# ANALOG.net
KiCad netlist of a schematic drawn in Altium Designer
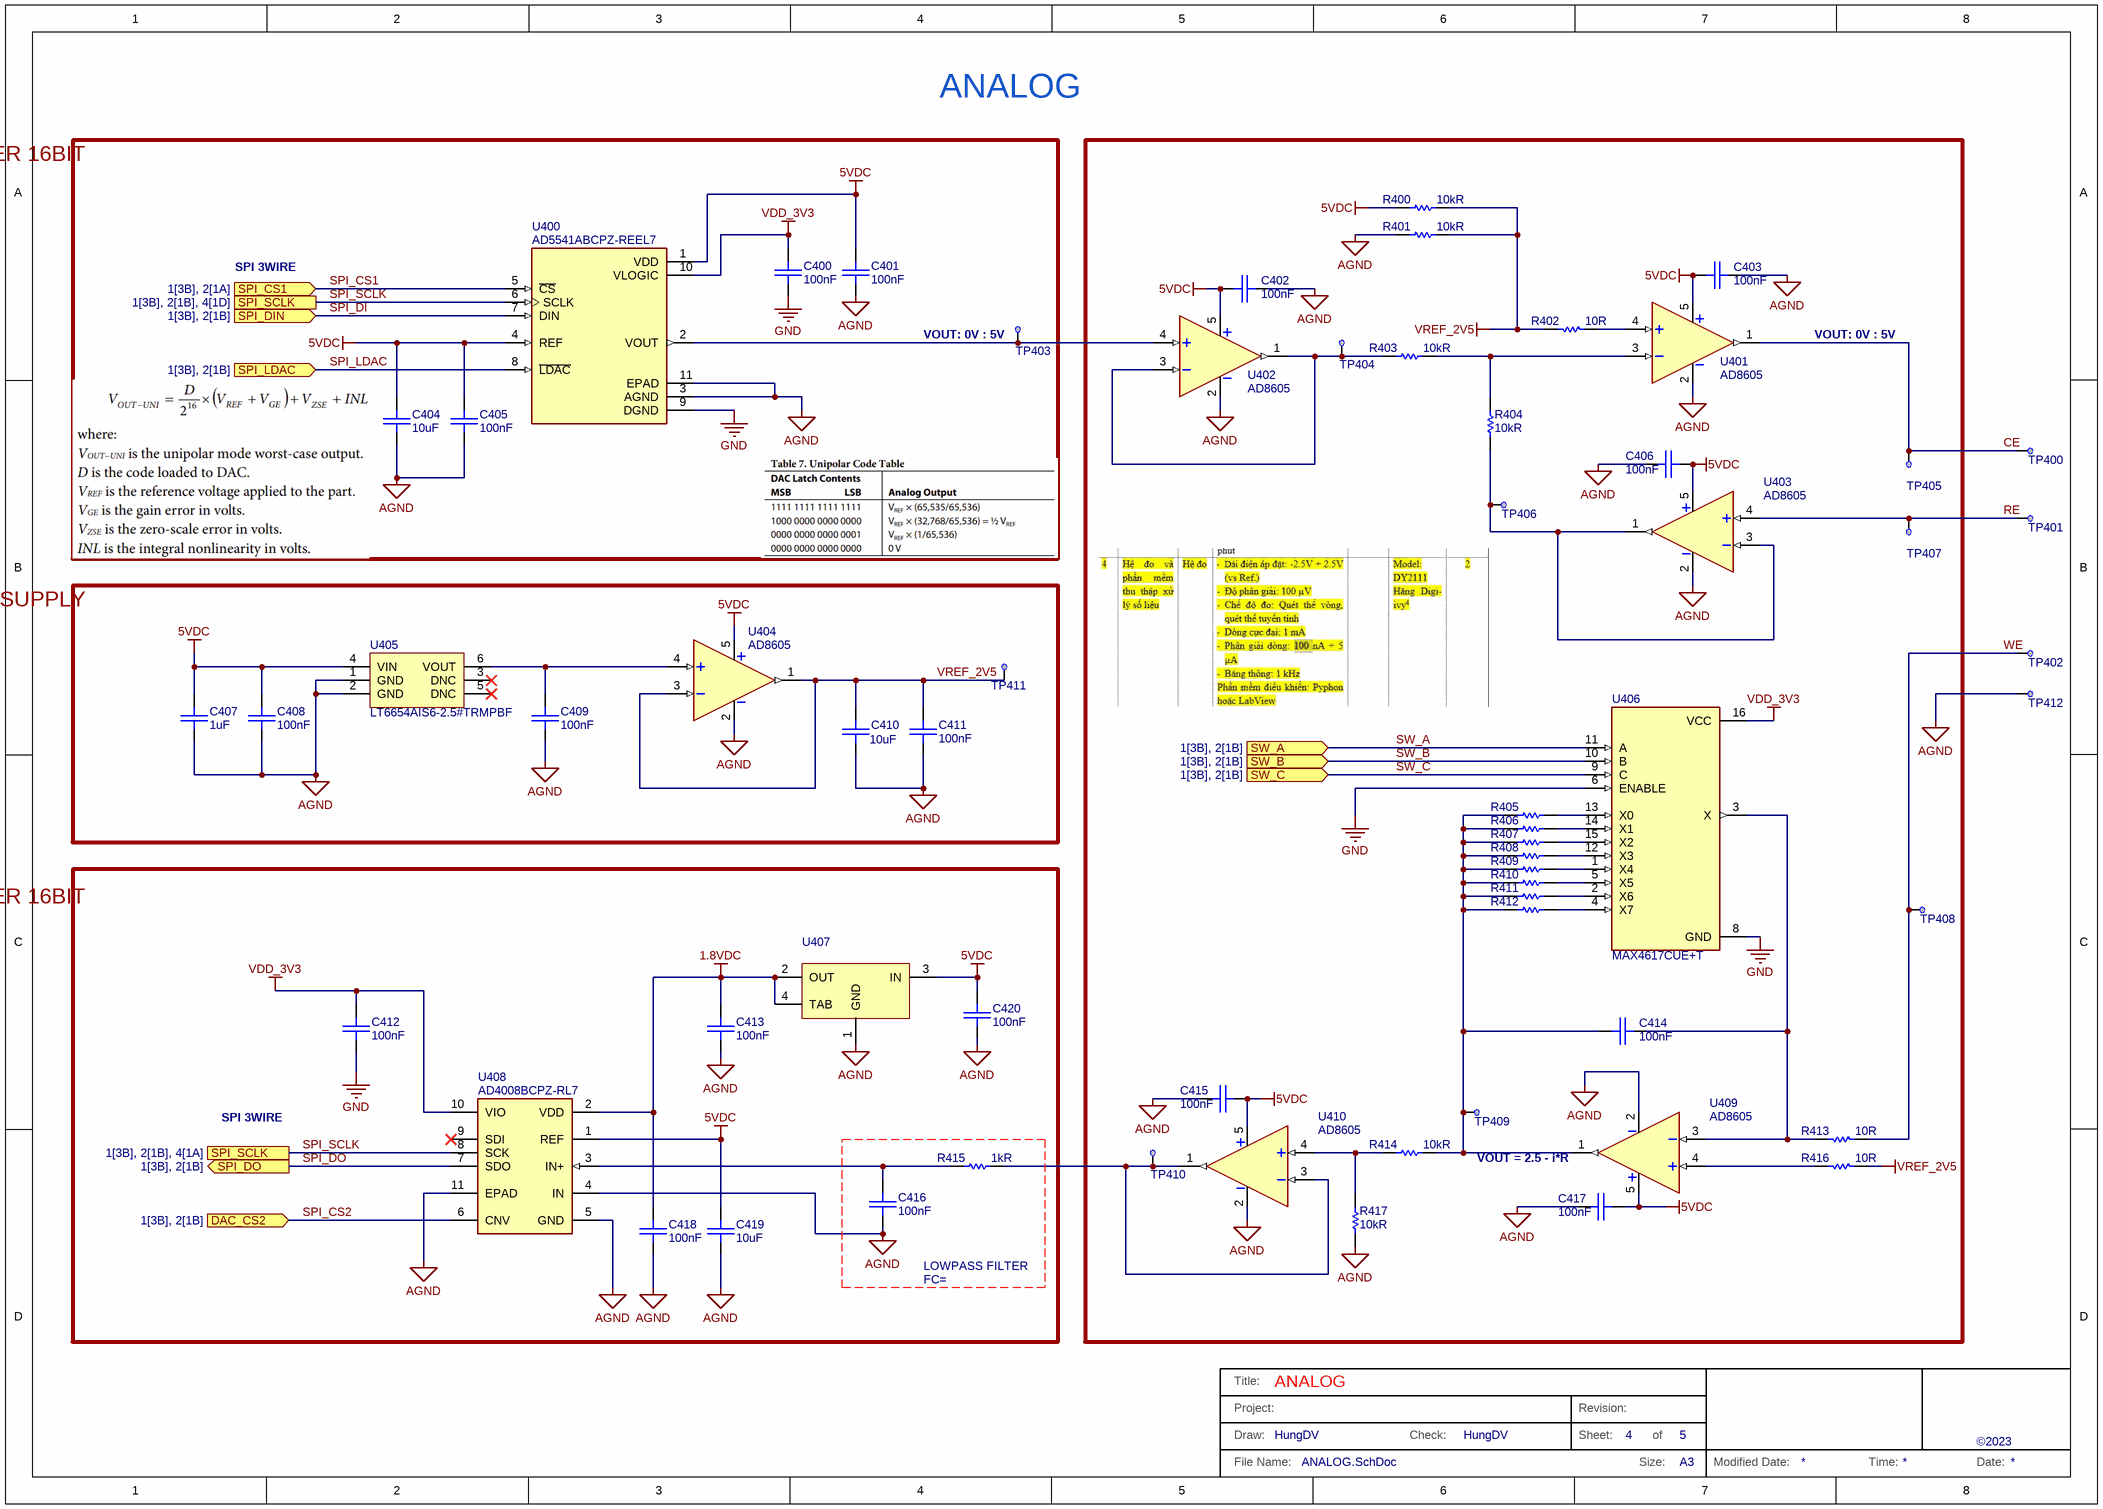
[diagram p0: ANALOG.SchDoc]

(export (version "E")
  (design (tool "Eeschema 10.0.6"))
  (components
    (comp (ref "C400")
      (value "100nF")
      (footprint "CAP0603-M")
      (description "CAP CER 100nF 16V X5R 0603")
      (fields (field (name "CAPACITANCE") "100nF"))
      (libsource (lib "Library") (part "CAP_10uF_0402"))
    )
    (comp (ref "C401")
      (value "100nF")
      (footprint "CAP0603-M")
      (description "CAP CER 100nF 16V X5R 0603")
      (fields (field (name "CAPACITANCE") "100nF"))
      (libsource (lib "Library") (part "CAP_10uF_0402"))
    )
    (comp (ref "C402")
      (value "100nF")
      (footprint "CAP0603-M")
      (description "CAP CER 100nF 16V X5R 0603")
      (fields (field (name "CAPACITANCE") "100nF"))
      (libsource (lib "Library") (part "CAP_10uF_0402"))
    )
    (comp (ref "C403")
      (value "100nF")
      (footprint "CAP0603-M")
      (description "CAP CER 100nF 16V X5R 0603")
      (fields (field (name "CAPACITANCE") "100nF"))
      (libsource (lib "Library") (part "CAP_10uF_0402"))
    )
    (comp (ref "C404")
      (value "10uF")
      (footprint "CAP0603-M")
      (description "CAP CER 10UF 16V X5R 0603")
      (fields (field (name "CAPACITANCE") "10uF"))
      (libsource (lib "EV_Mainboard") (part "CAP_10uF_0402"))
    )
    (comp (ref "C405")
      (value "100nF")
      (footprint "CAP0603-M")
      (description "CAP CER 100nF 16V X5R 0603")
      (fields (field (name "CAPACITANCE") "100nF"))
      (libsource (lib "Library") (part "CAP_10uF_0402"))
    )
    (comp (ref "C406")
      (value "100nF")
      (footprint "CAP0603-M")
      (description "CAP CER 100nF 16V X5R 0603")
      (fields (field (name "CAPACITANCE") "100nF"))
      (libsource (lib "Library") (part "CAP_10uF_0402"))
    )
    (comp (ref "C407")
      (value "10uF")
      (footprint "CAP0603-M")
      (description "CAP CER 10UF 16V X5R 0603")
      (fields (field (name "CAPACITANCE") "1uF"))
      (libsource (lib "Library") (part "CAP_10uF_0402"))
    )
    (comp (ref "C408")
      (value "100nF")
      (footprint "CAP0603-M")
      (description "CAP CER 100nF 16V X5R 0603")
      (fields (field (name "CAPACITANCE") "100nF"))
      (libsource (lib "Library") (part "CAP_10uF_0402"))
    )
    (comp (ref "C409")
      (value "100nF")
      (footprint "CAP0603-M")
      (description "CAP CER 100nF 16V X5R 0603")
      (fields (field (name "CAPACITANCE") "100nF"))
      (libsource (lib "Library") (part "CAP_10uF_0402"))
    )
    (comp (ref "C410")
      (value "10uF")
      (footprint "CAP0603-M")
      (description "CAP CER 10UF 16V X5R 0603")
      (fields (field (name "CAPACITANCE") "10uF"))
      (libsource (lib "EV_Mainboard") (part "CAP_10uF_0402"))
    )
    (comp (ref "C411")
      (value "100nF")
      (footprint "CAP0603-M")
      (description "CAP CER 100nF 16V X5R 0603")
      (fields (field (name "CAPACITANCE") "100nF"))
      (libsource (lib "Library") (part "CAP_10uF_0402"))
    )
    (comp (ref "C412")
      (value "100nF")
      (footprint "CAP0603-M")
      (description "CAP CER 100nF 16V X5R 0603")
      (fields (field (name "CAPACITANCE") "100nF"))
      (libsource (lib "Library") (part "CAP_10uF_0402"))
    )
    (comp (ref "C413")
      (value "100nF")
      (footprint "CAP0603-M")
      (description "CAP CER 100nF 16V X5R 0603")
      (fields (field (name "CAPACITANCE") "100nF"))
      (libsource (lib "Library") (part "CAP_10uF_0402"))
    )
    (comp (ref "C414")
      (value "100nF")
      (footprint "CAP0603-M")
      (description "CAP CER 100nF 16V X5R 0603")
      (fields (field (name "CAPACITANCE") "100nF"))
      (libsource (lib "Library") (part "CAP_10uF_0402"))
    )
    (comp (ref "C415")
      (value "100nF")
      (footprint "CAP0603-M")
      (description "CAP CER 100nF 16V X5R 0603")
      (fields (field (name "CAPACITANCE") "100nF"))
      (libsource (lib "Library") (part "CAP_10uF_0402"))
    )
    (comp (ref "C416")
      (value "100nF")
      (footprint "CAP0603-M")
      (description "CAP CER 100nF 16V X5R 0603")
      (fields (field (name "CAPACITANCE") "100nF"))
      (libsource (lib "Library") (part "CAP_10uF_0402"))
    )
    (comp (ref "C417")
      (value "100nF")
      (footprint "CAP0603-M")
      (description "CAP CER 100nF 16V X5R 0603")
      (fields (field (name "CAPACITANCE") "100nF"))
      (libsource (lib "Library") (part "CAP_10uF_0402"))
    )
    (comp (ref "C418")
      (value "100nF")
      (footprint "CAP0603-M")
      (description "CAP CER 100nF 16V X5R 0603")
      (fields (field (name "CAPACITANCE") "100nF"))
      (libsource (lib "Library") (part "CAP_10uF_0402"))
    )
    (comp (ref "C419")
      (value "10uF")
      (footprint "CAP0603-M")
      (description "CAP CER 10UF 16V X5R 0603")
      (fields (field (name "CAPACITANCE") "10uF"))
      (libsource (lib "Library") (part "CAP_10uF_0402"))
    )
    (comp (ref "C420")
      (value "100nF")
      (footprint "CAP0603-M")
      (description "CAP CER 100nF 16V X5R 0603")
      (fields (field (name "CAPACITANCE") "100nF"))
      (libsource (lib "Library") (part "CAP_10uF_0402"))
    )
    (comp (ref "R400")
      (value "10kR")
      (footprint "R_0603")
      (description "RES SMD 10K OHM 1% 1/8W 0603")
      (libsource (lib "X8.1.1_PCB_MAIN") (part "RES_10K_0201"))
    )
    (comp (ref "R401")
      (value "10kR")
      (footprint "R_0603")
      (description "RES SMD 10K OHM 1% 1/8W 0603")
      (libsource (lib "X8.1.1_PCB_MAIN") (part "RES_10K_0201"))
    )
    (comp (ref "R402")
      (value "10R")
      (footprint "R_0603")
      (description "RES SMD 10R OHM 1% 1/8W 0603")
      (libsource (lib "X8.1.1_PCB_MAIN") (part "RES_10K_0201"))
    )
    (comp (ref "R403")
      (value "10kR")
      (footprint "R_0603")
      (description "RES SMD 10K OHM 1% 1/8W 0603")
      (libsource (lib "X8.1.1_PCB_MAIN") (part "RES_10K_0201"))
    )
    (comp (ref "R404")
      (value "10kR")
      (footprint "R_0603")
      (description "RES SMD 10K OHM 1% 1/8W 0603")
      (libsource (lib "X8.1.1_PCB_MAIN") (part "RES_10K_0201"))
    )
    (comp (ref "R405")
      (value "RES 11.3K OHM 1% 1/20W 0201")
      (footprint "R_0603")
      (description "11.3kOhms ±1% 0.05W, 1/20W Chip Resistor 0201 (0603 Metric) Moisture Resistant Thick Film")
      (libsource (lib "X8.1.1_PCB_MAIN") (part "RES_10K_0201"))
    )
    (comp (ref "R406")
      (value "RES 11.3K OHM 1% 1/20W 0201")
      (footprint "R_0603")
      (description "11.3kOhms ±1% 0.05W, 1/20W Chip Resistor 0201 (0603 Metric) Moisture Resistant Thick Film")
      (libsource (lib "X8.1.1_PCB_MAIN") (part "RES_10K_0201"))
    )
    (comp (ref "R407")
      (value "RES 11.3K OHM 1% 1/20W 0201")
      (footprint "R_0603")
      (description "11.3kOhms ±1% 0.05W, 1/20W Chip Resistor 0201 (0603 Metric) Moisture Resistant Thick Film")
      (libsource (lib "X8.1.1_PCB_MAIN") (part "RES_10K_0201"))
    )
    (comp (ref "R408")
      (value "RES 11.3K OHM 1% 1/20W 0201")
      (footprint "R_0603")
      (description "11.3kOhms ±1% 0.05W, 1/20W Chip Resistor 0201 (0603 Metric) Moisture Resistant Thick Film")
      (libsource (lib "X8.1.1_PCB_MAIN") (part "RES_10K_0201"))
    )
    (comp (ref "R409")
      (value "RES 11.3K OHM 1% 1/20W 0201")
      (footprint "R_0603")
      (description "11.3kOhms ±1% 0.05W, 1/20W Chip Resistor 0201 (0603 Metric) Moisture Resistant Thick Film")
      (libsource (lib "X8.1.1_PCB_MAIN") (part "RES_10K_0201"))
    )
    (comp (ref "R410")
      (value "RES 11.3K OHM 1% 1/20W 0201")
      (footprint "R_0603")
      (description "11.3kOhms ±1% 0.05W, 1/20W Chip Resistor 0201 (0603 Metric) Moisture Resistant Thick Film")
      (libsource (lib "X8.1.1_PCB_MAIN") (part "RES_10K_0201"))
    )
    (comp (ref "R411")
      (value "RES 11.3K OHM 1% 1/20W 0201")
      (footprint "R_0603")
      (description "11.3kOhms ±1% 0.05W, 1/20W Chip Resistor 0201 (0603 Metric) Moisture Resistant Thick Film")
      (libsource (lib "X8.1.1_PCB_MAIN") (part "RES_10K_0201"))
    )
    (comp (ref "R412")
      (value "RES 11.3K OHM 1% 1/20W 0201")
      (footprint "R_0603")
      (description "11.3kOhms ±1% 0.05W, 1/20W Chip Resistor 0201 (0603 Metric) Moisture Resistant Thick Film")
      (libsource (lib "X8.1.1_PCB_MAIN") (part "RES_10K_0201"))
    )
    (comp (ref "R413")
      (value "10R")
      (footprint "R_0603")
      (description "RES SMD 10R OHM 1% 1/8W 0603")
      (libsource (lib "X8.1.1_PCB_MAIN") (part "RES_10K_0201"))
    )
    (comp (ref "R414")
      (value "10kR")
      (footprint "R_0603")
      (description "RES SMD 10K OHM 1% 1/8W 0603")
      (libsource (lib "X8.1.1_PCB_MAIN") (part "RES_10K_0201"))
    )
    (comp (ref "R415")
      (value "1kR")
      (footprint "R_0603")
      (description "RES SMD 1K OHM 1% 1/8W 0603")
      (libsource (lib "X8.1.1_PCB_MAIN") (part "RES_10K_0201"))
    )
    (comp (ref "R416")
      (value "10R")
      (footprint "R_0603")
      (description "RES SMD 10R OHM 1% 1/8W 0603")
      (libsource (lib "X8.1.1_PCB_MAIN") (part "RES_10K_0201"))
    )
    (comp (ref "R417")
      (value "10kR")
      (footprint "R_0603")
      (description "RES SMD 10K OHM 1% 1/8W 0603")
      (libsource (lib "X8.1.1_PCB_MAIN") (part "RES_10K_0201"))
    )
    (comp (ref "TP400")
      (value "SIREN_EN")
      (footprint "TPH")
      (description "Test_Point_1mm")
      (libsource (lib "Selex_Component_Lib") (part "Test_Point_1mm"))
    )
    (comp (ref "TP401")
      (value "SIREN_EN")
      (footprint "TPH")
      (description "Test_Point_1mm")
      (libsource (lib "Selex_Component_Lib") (part "Test_Point_1mm"))
    )
    (comp (ref "TP402")
      (value "SIREN_EN")
      (footprint "TPH")
      (description "Test_Point_1mm")
      (libsource (lib "Selex_Component_Lib") (part "Test_Point_1mm"))
    )
    (comp (ref "TP403")
      (value "VDAC")
      (footprint "TPH")
      (description "Test_Point_1mm")
      (libsource (lib "Selex_Component_Lib") (part "Test_Point_1mm"))
    )
    (comp (ref "TP404")
      (value "V1")
      (footprint "TPH")
      (description "Test_Point_1mm")
      (libsource (lib "Selex_Component_Lib") (part "Test_Point_1mm"))
    )
    (comp (ref "TP405")
      (value "VCE")
      (footprint "TPH")
      (description "Test_Point_1mm")
      (libsource (lib "Selex_Component_Lib") (part "Test_Point_1mm"))
    )
    (comp (ref "TP406")
      (value "VREFB")
      (footprint "TPH")
      (description "Test_Point_1mm")
      (libsource (lib "Selex_Component_Lib") (part "Test_Point_1mm"))
    )
    (comp (ref "TP407")
      (value "VRE")
      (footprint "TPH")
      (description "Test_Point_1mm")
      (libsource (lib "Selex_Component_Lib") (part "Test_Point_1mm"))
    )
    (comp (ref "TP408")
      (value "VWE")
      (footprint "TPH")
      (description "Test_Point_1mm")
      (libsource (lib "Selex_Component_Lib") (part "Test_Point_1mm"))
    )
    (comp (ref "TP409")
      (value "VIR")
      (footprint "TPH")
      (description "Test_Point_1mm")
      (libsource (lib "Selex_Component_Lib") (part "Test_Point_1mm"))
    )
    (comp (ref "TP410")
      (value "VADC")
      (footprint "TPH")
      (description "Test_Point_1mm")
      (libsource (lib "Selex_Component_Lib") (part "Test_Point_1mm"))
    )
    (comp (ref "TP411")
      (value "VREF")
      (footprint "TPH")
      (description "Test_Point_1mm")
      (libsource (lib "Selex_Component_Lib") (part "Test_Point_1mm"))
    )
    (comp (ref "TP412")
      (value "SIREN_EN")
      (footprint "TPH")
      (description "Test_Point_1mm")
      (libsource (lib "Selex_Component_Lib") (part "Test_Point_1mm"))
    )
    (comp (ref "U400")
      (value "AD5541ABCPZ-REEL7")
      (footprint "SON50P300X300X80-11N")
      (description "2.7 V to 5.5 V, Serial-Input, Voltage-Output, 16-/12-Bit nanoDACÂ™ in 8-lead 3 mm Ã— 3 mm LFCSP")
      (libsource (lib "Library") (part "AD5541ABCPZ-REEL7"))
    )
    (comp (ref "U401")
      (value "AD8605")
      (footprint "SOT95P280X145-5N")
      (description "IC OPAMP GP 1 CIRCUIT SOT23-5")
      (libsource (lib "Library") (part "AD8605"))
    )
    (comp (ref "U402")
      (value "AD8605")
      (footprint "SOT95P280X145-5N")
      (description "IC OPAMP GP 1 CIRCUIT SOT23-5")
      (libsource (lib "Library") (part "AD8605"))
    )
    (comp (ref "U403")
      (value "AD8605")
      (footprint "SOT95P280X145-5N")
      (description "IC OPAMP GP 1 CIRCUIT SOT23-5")
      (libsource (lib "Library") (part "AD8605"))
    )
    (comp (ref "U404")
      (value "AD8605")
      (footprint "SOT95P280X145-5N")
      (description "IC OPAMP GP 1 CIRCUIT SOT23-5")
      (libsource (lib "Library") (part "AD8605"))
    )
    (comp (ref "U405")
      (value "LT6654AIS6-2.5#TRMPBF")
      (footprint "SOT95P280X145-6N")
      (description "IC VREF SERIES 0.05% TSOT23-6")
      (libsource (lib "Library") (part "LT6654AIS6-2.5#TRMPBF"))
    )
    (comp (ref "U406")
      (value "MAX4617CUE+T")
      (footprint "TSOP65P640X110-16N")
      (description "IC MUX 8:1 10OHM 16TSSOP")
      (libsource (lib "Library") (part "MAX4617CUE+"))
    )
    (comp (ref "U407")
      (value "LM1117-3.3")
      (footprint "SOT223-4")
      (description "IC REG LINEAR 3.3V 1A SOT223")
      (fields (field (name "MANUFACTURER") "DIODE"))
      (libsource (lib "Selex_Component_Lib") (part "AZ1117IH-3.3TRG1"))
    )
    (comp (ref "U408")
      (value "AD4008BCPZ-RL7")
      (footprint "SON50P300X300X80-11N")
      (description "No Description Available")
      (libsource (lib "Library") (part "AD4008BCPZ-RL7"))
    )
    (comp (ref "U409")
      (value "AD8605")
      (footprint "SOT95P280X145-5N")
      (description "IC OPAMP GP 1 CIRCUIT SOT23-5")
      (libsource (lib "Library") (part "AD8605"))
    )
    (comp (ref "U410")
      (value "AD8605")
      (footprint "SOT95P280X145-5N")
      (description "IC OPAMP GP 1 CIRCUIT SOT23-5")
      (libsource (lib "Library") (part "AD8605"))
    )
  )
  (nets
    (net (code "1") (name "/CE") (class "Default")
      (node (ref "TP400") (pin "1") (pinfunction "TP_1") (pintype "passive"))
      (node (ref "TP405") (pin "1") (pinfunction "TP_1") (pintype "passive"))
      (node (ref "U401") (pin "1") (pinfunction "OUT_1") (pintype "output"))
    )
    (net (code "2") (name "/RE") (class "Default")
      (node (ref "TP401") (pin "1") (pinfunction "TP_1") (pintype "passive"))
      (node (ref "TP407") (pin "1") (pinfunction "TP_1") (pintype "passive"))
      (node (ref "U403") (pin "4") (pinfunction "-IN_4") (pintype "input"))
    )
    (net (code "3") (name "/SPI_CS1") (class "Default")
      (node (ref "U400") (pin "5") (pinfunction "~{CS}_5") (pintype "input"))
    )
    (net (code "4") (name "/SPI_CS2") (class "Default")
      (node (ref "U408") (pin "6") (pinfunction "CNV_6") (pintype "passive"))
    )
    (net (code "5") (name "/SPI_DI") (class "Default")
      (node (ref "U400") (pin "7") (pinfunction "DIN_7") (pintype "input"))
    )
    (net (code "6") (name "/SPI_DO") (class "Default")
      (node (ref "U408") (pin "7") (pinfunction "SDO_7") (pintype "passive"))
    )
    (net (code "7") (name "/SPI_LDAC") (class "Default")
      (node (ref "U400") (pin "8") (pinfunction "~{LDAC}_8") (pintype "input"))
    )
    (net (code "8") (name "/SPI_SCLK") (class "Default")
      (node (ref "U400") (pin "6") (pinfunction "SCLK_6") (pintype "input"))
      (node (ref "U408") (pin "8") (pinfunction "SCK_8") (pintype "passive"))
    )
    (net (code "9") (name "/SW_A") (class "Default")
      (node (ref "U406") (pin "11") (pinfunction "A_11") (pintype "input"))
    )
    (net (code "10") (name "/SW_B") (class "Default")
      (node (ref "U406") (pin "10") (pinfunction "B_10") (pintype "input"))
    )
    (net (code "11") (name "/SW_C") (class "Default")
      (node (ref "U406") (pin "9") (pinfunction "C_9") (pintype "input"))
    )
    (net (code "12") (name "/WE") (class "Default")
      (node (ref "R413") (pin "2") (pintype "passive"))
      (node (ref "TP402") (pin "1") (pinfunction "TP_1") (pintype "passive"))
      (node (ref "TP408") (pin "1") (pinfunction "TP_1") (pintype "passive"))
    )
    (net (code "13") (name "1.8VDC") (class "Default")
      (node (ref "C413") (pin "2") (pinfunction "2_2") (pintype "passive"))
      (node (ref "C418") (pin "2") (pinfunction "2_2") (pintype "passive"))
      (node (ref "U407") (pin "2") (pinfunction "OUT_2") (pintype "power_in"))
      (node (ref "U407") (pin "4") (pinfunction "TAB_4") (pintype "passive"))
      (node (ref "U408") (pin "2") (pinfunction "VDD_2") (pintype "power_in"))
    )
    (net (code "14") (name "5VDC") (class "Default")
      (node (ref "C401") (pin "2") (pinfunction "2_2") (pintype "passive"))
      (node (ref "C402") (pin "2") (pinfunction "2_2") (pintype "passive"))
      (node (ref "C403") (pin "2") (pinfunction "2_2") (pintype "passive"))
      (node (ref "C404") (pin "2") (pinfunction "2_2") (pintype "passive"))
      (node (ref "C405") (pin "2") (pinfunction "2_2") (pintype "passive"))
      (node (ref "C406") (pin "2") (pinfunction "2_2") (pintype "passive"))
      (node (ref "C407") (pin "2") (pinfunction "2_2") (pintype "passive"))
      (node (ref "C408") (pin "2") (pinfunction "2_2") (pintype "passive"))
      (node (ref "C415") (pin "2") (pinfunction "2_2") (pintype "passive"))
      (node (ref "C417") (pin "2") (pinfunction "2_2") (pintype "passive"))
      (node (ref "C419") (pin "2") (pinfunction "2_2") (pintype "passive"))
      (node (ref "C420") (pin "2") (pinfunction "2_2") (pintype "passive"))
      (node (ref "R400") (pin "2") (pintype "passive"))
      (node (ref "U400") (pin "1") (pinfunction "VDD_1") (pintype "power_in"))
      (node (ref "U400") (pin "4") (pinfunction "REF_4") (pintype "input"))
      (node (ref "U401") (pin "5") (pinfunction "V+_5") (pintype "passive"))
      (node (ref "U402") (pin "5") (pinfunction "V+_5") (pintype "passive"))
      (node (ref "U403") (pin "5") (pinfunction "V+_5") (pintype "passive"))
      (node (ref "U404") (pin "5") (pinfunction "V+_5") (pintype "passive"))
      (node (ref "U405") (pin "4") (pinfunction "VIN_4") (pintype "passive"))
      (node (ref "U407") (pin "3") (pinfunction "IN_3") (pintype "power_in"))
      (node (ref "U408") (pin "1") (pinfunction "REF_1") (pintype "passive"))
      (node (ref "U409") (pin "5") (pinfunction "V+_5") (pintype "passive"))
      (node (ref "U410") (pin "5") (pinfunction "V+_5") (pintype "passive"))
    )
    (net (code "15") (name "AGND") (class "Default")
      (node (ref "C401") (pin "1") (pinfunction "1_1") (pintype "passive"))
      (node (ref "C402") (pin "1") (pinfunction "1_1") (pintype "passive"))
      (node (ref "C403") (pin "1") (pinfunction "1_1") (pintype "passive"))
      (node (ref "C404") (pin "1") (pinfunction "1_1") (pintype "passive"))
      (node (ref "C405") (pin "1") (pinfunction "1_1") (pintype "passive"))
      (node (ref "C406") (pin "1") (pinfunction "1_1") (pintype "passive"))
      (node (ref "C407") (pin "1") (pinfunction "1_1") (pintype "passive"))
      (node (ref "C408") (pin "1") (pinfunction "1_1") (pintype "passive"))
      (node (ref "C409") (pin "1") (pinfunction "1_1") (pintype "passive"))
      (node (ref "C410") (pin "1") (pinfunction "1_1") (pintype "passive"))
      (node (ref "C411") (pin "1") (pinfunction "1_1") (pintype "passive"))
      (node (ref "C413") (pin "1") (pinfunction "1_1") (pintype "passive"))
      (node (ref "C415") (pin "1") (pinfunction "1_1") (pintype "passive"))
      (node (ref "C416") (pin "1") (pinfunction "1_1") (pintype "passive"))
      (node (ref "C417") (pin "1") (pinfunction "1_1") (pintype "passive"))
      (node (ref "C418") (pin "1") (pinfunction "1_1") (pintype "passive"))
      (node (ref "C419") (pin "1") (pinfunction "1_1") (pintype "passive"))
      (node (ref "C420") (pin "1") (pinfunction "1_1") (pintype "passive"))
      (node (ref "R401") (pin "2") (pintype "passive"))
      (node (ref "R417") (pin "2") (pintype "passive"))
      (node (ref "TP412") (pin "1") (pinfunction "TP_1") (pintype "passive"))
      (node (ref "U400") (pin "11") (pinfunction "EPAD_11") (pintype "power_in"))
      (node (ref "U400") (pin "3") (pinfunction "AGND_3") (pintype "power_in"))
      (node (ref "U401") (pin "2") (pinfunction "V-_2") (pintype "passive"))
      (node (ref "U402") (pin "2") (pinfunction "V-_2") (pintype "passive"))
      (node (ref "U403") (pin "2") (pinfunction "V-_2") (pintype "passive"))
      (node (ref "U404") (pin "2") (pinfunction "V-_2") (pintype "passive"))
      (node (ref "U405") (pin "1") (pinfunction "GND_1") (pintype "passive"))
      (node (ref "U405") (pin "2") (pinfunction "GND_2") (pintype "passive"))
      (node (ref "U407") (pin "1") (pinfunction "GND_1") (pintype "power_in"))
      (node (ref "U408") (pin "11") (pinfunction "EPAD_11") (pintype "passive"))
      (node (ref "U408") (pin "4") (pinfunction "IN_4") (pintype "passive"))
      (node (ref "U408") (pin "5") (pinfunction "GND_5") (pintype "power_in"))
      (node (ref "U409") (pin "2") (pinfunction "V-_2") (pintype "passive"))
      (node (ref "U410") (pin "2") (pinfunction "V-_2") (pintype "passive"))
    )
    (net (code "16") (name "GND") (class "Default")
      (node (ref "C400") (pin "1") (pinfunction "1_1") (pintype "passive"))
      (node (ref "C412") (pin "1") (pinfunction "1_1") (pintype "passive"))
      (node (ref "U400") (pin "9") (pinfunction "DGND_9") (pintype "power_in"))
      (node (ref "U406") (pin "6") (pinfunction "ENABLE_6") (pintype "input"))
      (node (ref "U406") (pin "8") (pinfunction "GND_8") (pintype "power_in"))
    )
    (net (code "17") (name "Net-(TP403-TP)") (class "Default")
      (node (ref "TP403") (pin "1") (pinfunction "TP_1") (pintype "passive"))
      (node (ref "U400") (pin "2") (pinfunction "VOUT_2") (pintype "output"))
      (node (ref "U402") (pin "4") (pinfunction "-IN_4") (pintype "input"))
    )
    (net (code "18") (name "Net-(TP404-TP)") (class "Default")
      (node (ref "R403") (pin "2") (pintype "passive"))
      (node (ref "TP404") (pin "1") (pinfunction "TP_1") (pintype "passive"))
      (node (ref "U402") (pin "1") (pinfunction "OUT_1") (pintype "output"))
      (node (ref "U402") (pin "3") (pinfunction "+IN_3") (pintype "input"))
    )
    (net (code "19") (name "Net-(TP406-TP)") (class "Default")
      (node (ref "R404") (pin "2") (pintype "passive"))
      (node (ref "TP406") (pin "1") (pinfunction "TP_1") (pintype "passive"))
      (node (ref "U403") (pin "1") (pinfunction "OUT_1") (pintype "output"))
      (node (ref "U403") (pin "3") (pinfunction "+IN_3") (pintype "input"))
    )
    (net (code "20") (name "Net-(TP409-TP)") (class "Default")
      (node (ref "C414") (pin "2") (pinfunction "2_2") (pintype "passive"))
      (node (ref "R405") (pin "2") (pintype "passive"))
      (node (ref "R406") (pin "2") (pintype "passive"))
      (node (ref "R407") (pin "2") (pintype "passive"))
      (node (ref "R408") (pin "2") (pintype "passive"))
      (node (ref "R409") (pin "2") (pintype "passive"))
      (node (ref "R410") (pin "2") (pintype "passive"))
      (node (ref "R411") (pin "2") (pintype "passive"))
      (node (ref "R412") (pin "2") (pintype "passive"))
      (node (ref "R414") (pin "1") (pintype "passive"))
      (node (ref "TP409") (pin "1") (pinfunction "TP_1") (pintype "passive"))
      (node (ref "U409") (pin "1") (pinfunction "OUT_1") (pintype "output"))
    )
    (net (code "21") (name "Net-(TP410-TP)") (class "Default")
      (node (ref "R415") (pin "1") (pintype "passive"))
      (node (ref "TP410") (pin "1") (pinfunction "TP_1") (pintype "passive"))
      (node (ref "U410") (pin "1") (pinfunction "OUT_1") (pintype "output"))
      (node (ref "U410") (pin "3") (pinfunction "+IN_3") (pintype "input"))
    )
    (net (code "22") (name "Net-(U401-+IN)") (class "Default")
      (node (ref "R403") (pin "1") (pintype "passive"))
      (node (ref "R404") (pin "1") (pintype "passive"))
      (node (ref "U401") (pin "3") (pinfunction "+IN_3") (pintype "input"))
    )
    (net (code "23") (name "Net-(U401--IN)") (class "Default")
      (node (ref "R402") (pin "2") (pintype "passive"))
      (node (ref "U401") (pin "4") (pinfunction "-IN_4") (pintype "input"))
    )
    (net (code "24") (name "Net-(U404--IN)") (class "Default")
      (node (ref "C409") (pin "2") (pinfunction "2_2") (pintype "passive"))
      (node (ref "U404") (pin "4") (pinfunction "-IN_4") (pintype "input"))
      (node (ref "U405") (pin "6") (pinfunction "VOUT_6") (pintype "passive"))
    )
    (net (code "25") (name "Net-(U406-X)") (class "Default")
      (node (ref "C414") (pin "1") (pinfunction "1_1") (pintype "passive"))
      (node (ref "R413") (pin "1") (pintype "passive"))
      (node (ref "U406") (pin "3") (pinfunction "X_3") (pintype "output"))
      (node (ref "U409") (pin "3") (pinfunction "+IN_3") (pintype "input"))
    )
    (net (code "26") (name "Net-(U406-X0)") (class "Default")
      (node (ref "R405") (pin "1") (pintype "passive"))
      (node (ref "U406") (pin "13") (pinfunction "X0_13") (pintype "input"))
    )
    (net (code "27") (name "Net-(U406-X1)") (class "Default")
      (node (ref "R406") (pin "1") (pintype "passive"))
      (node (ref "U406") (pin "14") (pinfunction "X1_14") (pintype "input"))
    )
    (net (code "28") (name "Net-(U406-X2)") (class "Default")
      (node (ref "R407") (pin "1") (pintype "passive"))
      (node (ref "U406") (pin "15") (pinfunction "X2_15") (pintype "input"))
    )
    (net (code "29") (name "Net-(U406-X3)") (class "Default")
      (node (ref "R408") (pin "1") (pintype "passive"))
      (node (ref "U406") (pin "12") (pinfunction "X3_12") (pintype "input"))
    )
    (net (code "30") (name "Net-(U406-X4)") (class "Default")
      (node (ref "R409") (pin "1") (pintype "passive"))
      (node (ref "U406") (pin "1") (pinfunction "X4_1") (pintype "input"))
    )
    (net (code "31") (name "Net-(U406-X5)") (class "Default")
      (node (ref "R410") (pin "1") (pintype "passive"))
      (node (ref "U406") (pin "5") (pinfunction "X5_5") (pintype "input"))
    )
    (net (code "32") (name "Net-(U406-X6)") (class "Default")
      (node (ref "R411") (pin "1") (pintype "passive"))
      (node (ref "U406") (pin "2") (pinfunction "X6_2") (pintype "input"))
    )
    (net (code "33") (name "Net-(U406-X7)") (class "Default")
      (node (ref "R412") (pin "1") (pintype "passive"))
      (node (ref "U406") (pin "4") (pinfunction "X7_4") (pintype "input"))
    )
    (net (code "34") (name "Net-(U408-IN+)") (class "Default")
      (node (ref "C416") (pin "2") (pinfunction "2_2") (pintype "passive"))
      (node (ref "R415") (pin "2") (pintype "passive"))
      (node (ref "U408") (pin "3") (pinfunction "IN+_3") (pintype "input"))
    )
    (net (code "35") (name "Net-(U409--IN)") (class "Default")
      (node (ref "R416") (pin "1") (pintype "passive"))
      (node (ref "U409") (pin "4") (pinfunction "-IN_4") (pintype "input"))
    )
    (net (code "36") (name "Net-(U410--IN)") (class "Default")
      (node (ref "R414") (pin "2") (pintype "passive"))
      (node (ref "R417") (pin "1") (pintype "passive"))
      (node (ref "U410") (pin "4") (pinfunction "-IN_4") (pintype "input"))
    )
    (net (code "37") (name "VDD_3V3") (class "Default")
      (node (ref "C400") (pin "2") (pinfunction "2_2") (pintype "passive"))
      (node (ref "C412") (pin "2") (pinfunction "2_2") (pintype "passive"))
      (node (ref "U400") (pin "10") (pinfunction "VLOGIC_10") (pintype "power_in"))
      (node (ref "U406") (pin "16") (pinfunction "VCC_16") (pintype "power_in"))
      (node (ref "U408") (pin "10") (pinfunction "VIO_10") (pintype "passive"))
    )
    (net (code "38") (name "VREF_2V5") (class "Default")
      (node (ref "C410") (pin "2") (pinfunction "2_2") (pintype "passive"))
      (node (ref "C411") (pin "2") (pinfunction "2_2") (pintype "passive"))
      (node (ref "R400") (pin "1") (pintype "passive"))
      (node (ref "R401") (pin "1") (pintype "passive"))
      (node (ref "R402") (pin "1") (pintype "passive"))
      (node (ref "R416") (pin "2") (pintype "passive"))
      (node (ref "TP411") (pin "1") (pinfunction "TP_1") (pintype "passive"))
      (node (ref "U404") (pin "1") (pinfunction "OUT_1") (pintype "output"))
      (node (ref "U404") (pin "3") (pinfunction "+IN_3") (pintype "input"))
    )
    (net (code "39") (name "unconnected-(U405-DNC-Pad3)") (class "Default")
      (node (ref "U405") (pin "3") (pinfunction "DNC_3") (pintype "passive+no_connect"))
    )
    (net (code "40") (name "unconnected-(U405-DNC-Pad5)") (class "Default")
      (node (ref "U405") (pin "5") (pinfunction "DNC_5") (pintype "passive+no_connect"))
    )
    (net (code "41") (name "unconnected-(U408-SDI-Pad9)") (class "Default")
      (node (ref "U408") (pin "9") (pinfunction "SDI_9") (pintype "passive+no_connect"))
    )
  )
)
